# Current_check.net
KiCad netlist of a schematic drawn in Altium Designer
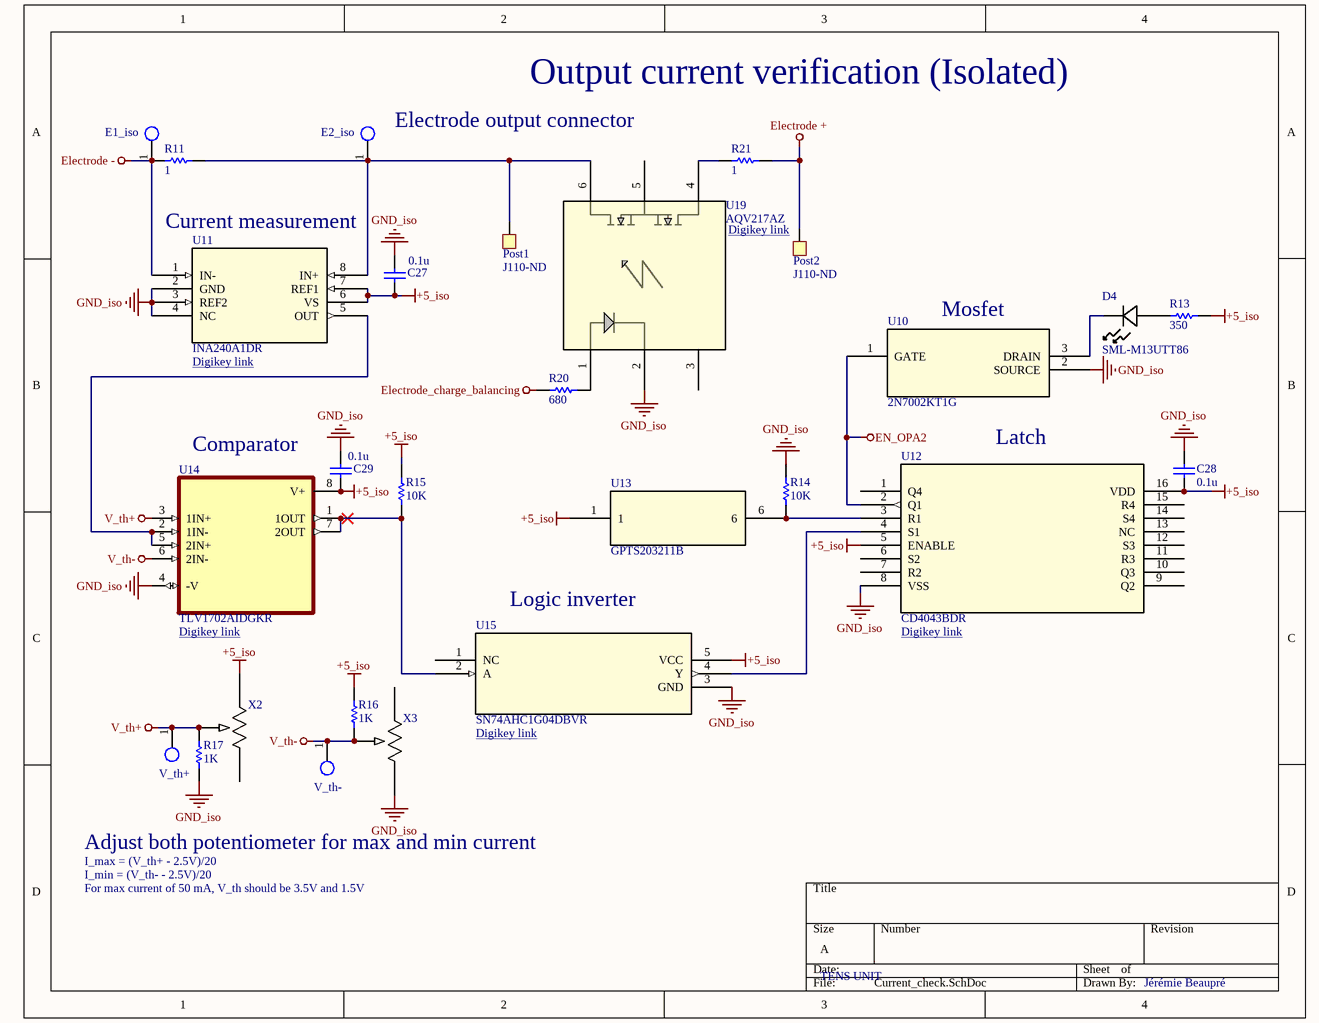
[diagram p0: Current_check.SchDoc]

(export (version "E")
  (design (tool "Eeschema 10.0.6"))
  (components
    (comp (ref "C27")
      (value "0.1u")
      (footprint "CAPC2012X150N")
      (description "Capacitor")
      (libsource (lib "Simulation Generic Components") (part "Capacitor"))
    )
    (comp (ref "C28")
      (value "0.1u")
      (footprint "CAPC2012X150N")
      (description "Capacitor")
      (libsource (lib "Simulation Generic Components") (part "Capacitor"))
    )
    (comp (ref "C29")
      (value "0.1u")
      (footprint "CAPC2012X150N")
      (description "Capacitor")
      (libsource (lib "Simulation Generic Components") (part "Capacitor"))
    )
    (comp (ref "D4")
      (value "SML-M13UTT86")
      (footprint "LED_SML-M13DT_ROM")
      (description "No Description Available")
      (fields (field (name "COPYRIGHT") "Copyright (C) 2026 Ultra Librarian. All rights reserved."))
      (libsource (lib "SML-M13UTT86") (part "SML-M13UTT86"))
    )
    (comp (ref "E1_iso")
      (value "Testpoint_1")
      (footprint "Testpoint1")
      (libsource (lib "My_lib") (part "Testpoint_1"))
    )
    (comp (ref "E2_iso")
      (value "Testpoint_1")
      (footprint "Testpoint1")
      (libsource (lib "My_lib") (part "Testpoint_1"))
    )
    (comp (ref "Post1") (value "J110-ND") (footprint "J110-ND") (libsource (lib "My_lib") (part "J110-ND")))
    (comp (ref "Post2") (value "J110-ND") (footprint "J110-ND") (libsource (lib "My_lib") (part "J110-ND")))
    (comp (ref "R11")
      (value "1")
      (footprint "Resistor_0805-M")
      (description "Resistor")
      (libsource (lib "Simulation Generic Components") (part "Resistor"))
    )
    (comp (ref "R13")
      (value "350")
      (footprint "Resistor_0805-M")
      (description "Resistor")
      (libsource (lib "Simulation Generic Components") (part "Resistor"))
    )
    (comp (ref "R14")
      (value "10K")
      (footprint "Resistor_0805-M")
      (description "Resistor")
      (libsource (lib "Simulation Generic Components") (part "Resistor"))
    )
    (comp (ref "R15")
      (value "10K")
      (footprint "Resistor_0805-M")
      (description "Resistor")
      (libsource (lib "Simulation Generic Components") (part "Resistor"))
    )
    (comp (ref "R16")
      (value "1K")
      (footprint "Resistor_0805-M")
      (description "Resistor")
      (libsource (lib "Simulation Generic Components") (part "Resistor"))
    )
    (comp (ref "R17")
      (value "1K")
      (footprint "Resistor_0805-M")
      (description "Resistor")
      (libsource (lib "Simulation Generic Components") (part "Resistor"))
    )
    (comp (ref "R20")
      (value "680")
      (footprint "Resistor_0805-M")
      (description "Resistor")
      (libsource (lib "Simulation Generic Components") (part "Resistor"))
    )
    (comp (ref "R21")
      (value "1")
      (footprint "Resistor_0805-M")
      (description "Resistor")
      (libsource (lib "Simulation Generic Components") (part "Resistor"))
    )
    (comp (ref "U10")
      (value "2N7002KT1G")
      (footprint "SOT-23_ONS")
      (description "Description")
      (fields (field (name "COPYRIGHT") "Copyright (C) 2026 Ultra Librarian. All rights reserved."))
      (libsource (lib "2N7002KT1G") (part "2N7002KT1G"))
    )
    (comp (ref "U11")
      (value "INA240A1DR")
      (footprint "D8_TEX")
      (fields (field (name "COPYRIGHT") "Copyright (C) 2025 Ultra Librarian. All rights reserved."))
      (libsource (lib "INA240A1DR") (part "INA240A1DR"))
    )
    (comp (ref "U12")
      (value "CD4043BDR")
      (footprint "D16")
      (description "CMOS Quad NOR R/S Latch with 3-State Outputs 16-SOIC -55 to 125")
      (fields (field (name "COPYRIGHT") "Copyright (C) 2025 Ultra Librarian. All rights reserved."))
      (libsource (lib "CD4043BDR") (part "CD4043BDR"))
    )
    (comp (ref "U13")
      (value "GPTS203211B")
      (footprint "SWITCH_03211B")
      (description "No Description Available")
      (fields (field (name "COPYRIGHT") "Copyright (C) 2026 Ultra Librarian. All rights reserved."))
      (libsource (lib "GPTS203211B") (part "GPTS203211B"))
    )
    (comp (ref "U14")
      (value "TLV1702AIDGKR")
      (footprint "SOP65P490X110-8N")
      (description "Dual high voltage, low power comparator")
      (fields (field (name "MF") "Texas Instruments"))
      (libsource (lib "TLV1702AIDGKR") (part "TLV1702AIDGKR"))
    )
    (comp (ref "U15")
      (value "SN74AHC1G04DBVR")
      (footprint "DBV5")
      (description "Single 2-V to 5.5-V inverter 5-SOT-23 -40 to 125")
      (fields (field (name "COPYRIGHT") "Copyright (C) 2026 Ultra Librarian. All rights reserved."))
      (libsource (lib "SN74AHC1G04DBVR") (part "SN74AHC1G04DBVR"))
    )
    (comp (ref "U19")
      (value "AQV217AZ")
      (footprint "DIP-6_SMD_PAN")
      (description "No Description Available")
      (fields (field (name "COPYRIGHT") "Copyright (C) 2026 Ultra Librarian. All rights reserved."))
      (libsource (lib "AQV217AZ") (part "AQV217AZ"))
    )
    (comp (ref "V_th+")
      (value "Testpoint_1")
      (footprint "Testpoint1")
      (libsource (lib "My_lib") (part "Testpoint_1"))
    )
    (comp (ref "V_th-")
      (value "Testpoint_1")
      (footprint "Testpoint1")
      (libsource (lib "My_lib") (part "Testpoint_1"))
    )
    (comp (ref "X2")
      (value "PV36W102C01B00")
      (footprint "POT_PV36W_MUR")
      (description "No Description Available")
      (fields (field (name "COPYRIGHT") "Copyright (C) 2026 Ultra Librarian. All rights reserved."))
      (libsource (lib "PV36W102C01B00") (part "PV36W102C01B00"))
    )
    (comp (ref "X3")
      (value "PV36W102C01B00")
      (footprint "POT_PV36W_MUR")
      (description "No Description Available")
      (fields (field (name "COPYRIGHT") "Copyright (C) 2026 Ultra Librarian. All rights reserved."))
      (libsource (lib "PV36W102C01B00") (part "PV36W102C01B00"))
    )
  )
  (nets
    (net (code "1") (name "+5_iso") (class "Default")
      (node (ref "C27") (pin "2") (pinfunction "2_2") (pintype "passive"))
      (node (ref "C28") (pin "2") (pinfunction "2_2") (pintype "passive"))
      (node (ref "C29") (pin "2") (pinfunction "2_2") (pintype "passive"))
      (node (ref "R13") (pin "2") (pinfunction "2_2") (pintype "passive"))
      (node (ref "R15") (pin "2") (pinfunction "2_2") (pintype "passive"))
      (node (ref "R16") (pin "2") (pinfunction "2_2") (pintype "passive"))
      (node (ref "U11") (pin "6") (pinfunction "VS_6") (pintype "power_in"))
      (node (ref "U11") (pin "7") (pinfunction "REF1_7") (pintype "input"))
      (node (ref "U12") (pin "16") (pinfunction "VDD_16") (pintype "power_in"))
      (node (ref "U12") (pin "5") (pinfunction "ENABLE_5") (pintype "passive"))
      (node (ref "U13") (pin "1") (pinfunction "1_1") (pintype "passive"))
      (node (ref "U14") (pin "8") (pinfunction "V+_8") (pintype "power_in"))
      (node (ref "U15") (pin "5") (pinfunction "VCC_5") (pintype "power_in"))
      (node (ref "X2") (pin "3") (pinfunction "3_3") (pintype "passive"))
    )
    (net (code "2") (name "EN_OPA2") (class "Default")
      (node (ref "U10") (pin "1") (pinfunction "GATE_1") (pintype "passive"))
      (node (ref "U12") (pin "2") (pinfunction "Q1_2") (pintype "output"))
    )
    (net (code "3") (name "Electrode +") (class "Default")
      (node (ref "Post2") (pin "1") (pinfunction "1_1") (pintype "passive"))
      (node (ref "R21") (pin "1") (pinfunction "1_1") (pintype "passive"))
    )
    (net (code "4") (name "Electrode -") (class "Default")
      (node (ref "E1_iso") (pin "1") (pinfunction "P1_1") (pintype "passive"))
      (node (ref "R11") (pin "1") (pinfunction "1_1") (pintype "passive"))
      (node (ref "U11") (pin "1") (pinfunction "IN-_1") (pintype "input"))
    )
    (net (code "5") (name "Electrode_charge_balancing") (class "Default")
      (node (ref "R20") (pin "2") (pinfunction "2_2") (pintype "passive"))
    )
    (net (code "6") (name "GND_iso") (class "Default")
      (node (ref "C27") (pin "1") (pinfunction "1_1") (pintype "passive"))
      (node (ref "C28") (pin "1") (pinfunction "1_1") (pintype "passive"))
      (node (ref "C29") (pin "1") (pinfunction "1_1") (pintype "passive"))
      (node (ref "R14") (pin "2") (pinfunction "2_2") (pintype "passive"))
      (node (ref "R17") (pin "1") (pinfunction "1_1") (pintype "passive"))
      (node (ref "U10") (pin "2") (pinfunction "SOURCE_2") (pintype "passive"))
      (node (ref "U11") (pin "2") (pinfunction "GND_2") (pintype "power_in"))
      (node (ref "U11") (pin "3") (pinfunction "REF2_3") (pintype "input"))
      (node (ref "U11") (pin "4") (pinfunction "NC_4") (pintype "passive"))
      (node (ref "U12") (pin "8") (pinfunction "VSS_8") (pintype "power_in"))
      (node (ref "U14") (pin "4") (pinfunction "-V_4") (pintype "bidirectional"))
      (node (ref "U15") (pin "3") (pinfunction "GND_3") (pintype "power_in"))
      (node (ref "U19") (pin "2") (pinfunction "3_2") (pintype "passive"))
      (node (ref "X3") (pin "1") (pinfunction "1_1") (pintype "passive"))
    )
    (net (code "7") (name "Net-(D4-Pad2)") (class "Default")
      (node (ref "D4") (pin "2") (pinfunction "2_2") (pintype "passive"))
      (node (ref "R13") (pin "1") (pinfunction "1_1") (pintype "passive"))
    )
    (net (code "8") (name "Net-(E2_iso-P1)") (class "Default")
      (node (ref "E2_iso") (pin "1") (pinfunction "P1_1") (pintype "passive"))
      (node (ref "Post1") (pin "1") (pinfunction "1_1") (pintype "passive"))
      (node (ref "R11") (pin "2") (pinfunction "2_2") (pintype "passive"))
      (node (ref "U11") (pin "8") (pinfunction "IN+_8") (pintype "input"))
      (node (ref "U19") (pin "6") (pinfunction "2_6") (pintype "passive"))
    )
    (net (code "9") (name "Net-(R20-Pad1)") (class "Default")
      (node (ref "R20") (pin "1") (pinfunction "1_1") (pintype "passive"))
      (node (ref "U19") (pin "1") (pinfunction "1_1") (pintype "passive"))
    )
    (net (code "10") (name "Net-(U10-DRAIN)") (class "Default")
      (node (ref "D4") (pin "1") (pinfunction "1_1") (pintype "passive"))
      (node (ref "U10") (pin "3") (pinfunction "DRAIN_3") (pintype "passive"))
    )
    (net (code "11") (name "Net-(U11-OUT)") (class "Default")
      (node (ref "U11") (pin "5") (pinfunction "OUT_5") (pintype "output"))
      (node (ref "U14") (pin "2") (pinfunction "1IN-_2") (pintype "input"))
      (node (ref "U14") (pin "5") (pinfunction "2IN+_5") (pintype "input"))
    )
    (net (code "12") (name "Net-(U12-R1)") (class "Default")
      (node (ref "R14") (pin "1") (pinfunction "1_1") (pintype "passive"))
      (node (ref "U12") (pin "3") (pinfunction "R1_3") (pintype "passive"))
      (node (ref "U13") (pin "6") (pinfunction "6_6") (pintype "passive"))
    )
    (net (code "13") (name "Net-(U12-S1)") (class "Default")
      (node (ref "U12") (pin "4") (pinfunction "S1_4") (pintype "passive"))
      (node (ref "U15") (pin "4") (pinfunction "Y_4") (pintype "output"))
    )
    (net (code "14") (name "Net-(U14-1OUT)") (class "Default")
      (node (ref "R15") (pin "1") (pinfunction "1_1") (pintype "passive"))
      (node (ref "U14") (pin "1") (pinfunction "1OUT_1") (pintype "output"))
      (node (ref "U14") (pin "7") (pinfunction "2OUT_7") (pintype "output"))
      (node (ref "U15") (pin "2") (pinfunction "A_2") (pintype "input"))
    )
    (net (code "15") (name "Net-(U19-6)") (class "Default")
      (node (ref "R21") (pin "2") (pinfunction "2_2") (pintype "passive"))
      (node (ref "U19") (pin "4") (pinfunction "6_4") (pintype "passive"))
    )
    (net (code "16") (name "V_th+") (class "Default")
      (node (ref "R17") (pin "2") (pinfunction "2_2") (pintype "passive"))
      (node (ref "U14") (pin "3") (pinfunction "1IN+_3") (pintype "input"))
      (node (ref "V_th+") (pin "1") (pinfunction "P1_1") (pintype "passive"))
      (node (ref "X2") (pin "2") (pinfunction "2_2") (pintype "passive"))
    )
    (net (code "17") (name "V_th-") (class "Default")
      (node (ref "R16") (pin "1") (pinfunction "1_1") (pintype "passive"))
      (node (ref "U14") (pin "6") (pinfunction "2IN-_6") (pintype "input"))
      (node (ref "V_th-") (pin "1") (pinfunction "P1_1") (pintype "passive"))
      (node (ref "X3") (pin "2") (pinfunction "2_2") (pintype "passive"))
    )
    (net (code "18") (name "unconnected-(U12-NC-Pad13)") (class "Default")
      (node (ref "U12") (pin "13") (pinfunction "NC_13") (pintype "passive"))
    )
    (net (code "19") (name "unconnected-(U12-Q2-Pad9)") (class "Default")
      (node (ref "U12") (pin "9") (pinfunction "Q2_9") (pintype "passive"))
    )
    (net (code "20") (name "unconnected-(U12-Q3-Pad10)") (class "Default")
      (node (ref "U12") (pin "10") (pinfunction "Q3_10") (pintype "passive"))
    )
    (net (code "21") (name "unconnected-(U12-Q4-Pad1)") (class "Default")
      (node (ref "U12") (pin "1") (pinfunction "Q4_1") (pintype "passive"))
    )
    (net (code "22") (name "unconnected-(U12-R2-Pad7)") (class "Default")
      (node (ref "U12") (pin "7") (pinfunction "R2_7") (pintype "passive"))
    )
    (net (code "23") (name "unconnected-(U12-R3-Pad11)") (class "Default")
      (node (ref "U12") (pin "11") (pinfunction "R3_11") (pintype "passive"))
    )
    (net (code "24") (name "unconnected-(U12-R4-Pad15)") (class "Default")
      (node (ref "U12") (pin "15") (pinfunction "R4_15") (pintype "passive"))
    )
    (net (code "25") (name "unconnected-(U12-S2-Pad6)") (class "Default")
      (node (ref "U12") (pin "6") (pinfunction "S2_6") (pintype "passive"))
    )
    (net (code "26") (name "unconnected-(U12-S3-Pad12)") (class "Default")
      (node (ref "U12") (pin "12") (pinfunction "S3_12") (pintype "passive"))
    )
    (net (code "27") (name "unconnected-(U12-S4-Pad14)") (class "Default")
      (node (ref "U12") (pin "14") (pinfunction "S4_14") (pintype "passive"))
    )
    (net (code "28") (name "unconnected-(U15-NC-Pad1)") (class "Default")
      (node (ref "U15") (pin "1") (pinfunction "NC_1") (pintype "passive"))
    )
    (net (code "29") (name "unconnected-(U19-4-Pad5)") (class "Default")
      (node (ref "U19") (pin "5") (pinfunction "4_5") (pintype "passive"))
    )
    (net (code "30") (name "unconnected-(U19-5-Pad3)") (class "Default")
      (node (ref "U19") (pin "3") (pinfunction "5_3") (pintype "passive"))
    )
    (net (code "31") (name "unconnected-(X2-Pad1)") (class "Default")
      (node (ref "X2") (pin "1") (pinfunction "1_1") (pintype "passive"))
    )
    (net (code "32") (name "unconnected-(X3-Pad3)") (class "Default")
      (node (ref "X3") (pin "3") (pinfunction "3_3") (pintype "passive"))
    )
  )
)
